# Power-LED.net
KiCad netlist of a schematic drawn in Altium Designer
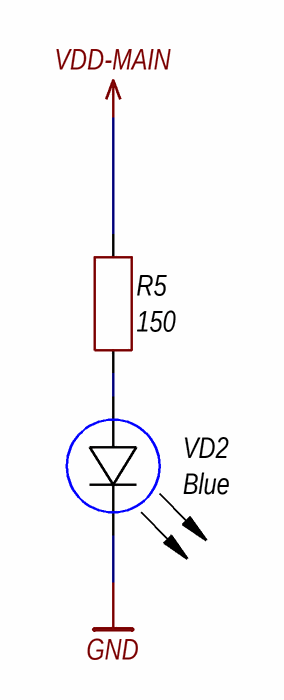
[diagram p0: Power-LED.SchDoc]

(export (version "E")
  (design (tool "Eeschema 10.0.6"))
  (components
    (comp (ref "R5") (value "150") (footprint "CH0402R") (libsource (lib "Discrete") (part "Resistor")))
    (comp (ref "VD2") (value "Blue") (footprint "CH0402LG") (libsource (lib "Discrete") (part "LED")))
  )
  (nets
    (net (code "1") (name "GND") (class "Default")
      (node (ref "VD2") (pin "2") (pinfunction "C_2") (pintype "passive"))
    )
    (net (code "2") (name "Net-(VD2-A)") (class "Default")
      (node (ref "R5") (pin "1") (pinfunction "1_1") (pintype "passive"))
      (node (ref "VD2") (pin "1") (pinfunction "A_1") (pintype "passive"))
    )
    (net (code "3") (name "VDD-MAIN") (class "Default")
      (node (ref "R5") (pin "2") (pinfunction "2_2") (pintype "passive"))
    )
  )
)
